# STlinkv21_STM8.net
KiCad netlist of a schematic drawn in Altium Designer
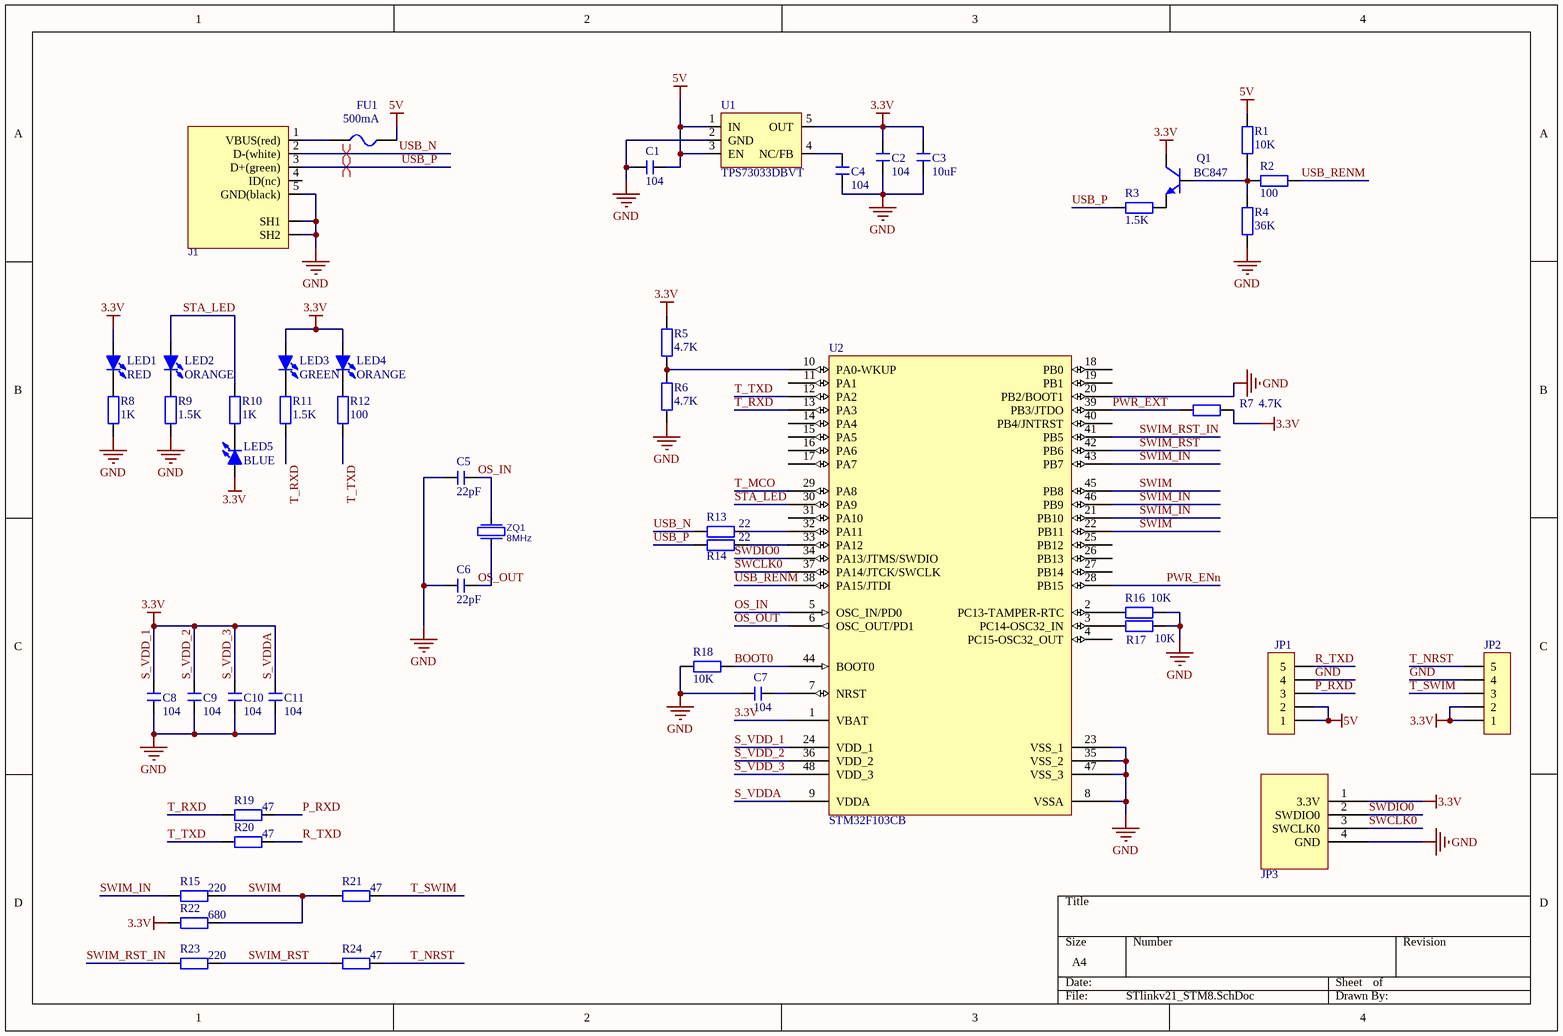
[diagram p0: STlinkv21_STM8.SchDoc]

(export (version "E")
  (design (tool "Eeschema 10.0.6"))
  (components
    (comp (ref "*") (value "JP3") (footprint "JP4") (libsource (lib "STlinkv21") (part "JP?")))
    (comp (ref "C1")
      (value "104")
      (footprint "C 0603_L")
      (description "无极性贴片电容")
      (fields (field (name "版权归属") "源创客"))
      (libsource (lib "3.1   - 电阻-电容-电感") (part "C"))
    )
    (comp (ref "C2")
      (value "104")
      (footprint "C 0603_L")
      (description "无极性贴片电容")
      (fields (field (name "版权归属") "源创客"))
      (libsource (lib "3.1   - 电阻-电容-电感") (part "C"))
    )
    (comp (ref "C3")
      (value "10uF")
      (footprint "C 0603_L")
      (description "无极性贴片电容")
      (fields (field (name "版权归属") "源创客"))
      (libsource (lib "3.1   - 电阻-电容-电感") (part "C"))
    )
    (comp (ref "C4")
      (value "104")
      (footprint "C 0603_L")
      (description "无极性贴片电容")
      (fields (field (name "版权归属") "源创客"))
      (libsource (lib "3.1   - 电阻-电容-电感") (part "C"))
    )
    (comp (ref "C5")
      (value "22pF")
      (footprint "C 0603_L")
      (description "无极性贴片电容")
      (fields (field (name "版权归属") "源创客"))
      (libsource (lib "3.1   - 电阻-电容-电感") (part "C"))
    )
    (comp (ref "C6")
      (value "22pF")
      (footprint "C 0603_L")
      (description "无极性贴片电容")
      (fields (field (name "版权归属") "源创客"))
      (libsource (lib "3.1   - 电阻-电容-电感") (part "C"))
    )
    (comp (ref "C7")
      (value "104")
      (footprint "C 0603_L")
      (description "无极性贴片电容")
      (fields (field (name "版权归属") "源创客"))
      (libsource (lib "3.1   - 电阻-电容-电感") (part "C"))
    )
    (comp (ref "C8")
      (value "104")
      (footprint "C 0603_L")
      (description "无极性贴片电容")
      (fields (field (name "版权归属") "源创客"))
      (libsource (lib "3.1   - 电阻-电容-电感") (part "C"))
    )
    (comp (ref "C9")
      (value "104")
      (footprint "C 0603_L")
      (description "无极性贴片电容")
      (fields (field (name "版权归属") "源创客"))
      (libsource (lib "3.1   - 电阻-电容-电感") (part "C"))
    )
    (comp (ref "C10")
      (value "104")
      (footprint "C 0603_L")
      (description "无极性贴片电容")
      (fields (field (name "版权归属") "源创客"))
      (libsource (lib "3.1   - 电阻-电容-电感") (part "C"))
    )
    (comp (ref "C11")
      (value "104")
      (footprint "C 0603_L")
      (description "无极性贴片电容")
      (fields (field (name "版权归属") "源创客"))
      (libsource (lib "3.1   - 电阻-电容-电感") (part "C"))
    )
    (comp (ref "FU1")
      (value "500mA")
      (footprint "FU 0805")
      (description "贴片保险丝")
      (fields (field (name "版权归属") "源创客"))
      (libsource (lib "10.1 - 保险丝-晶振") (part "FU"))
    )
    (comp (ref "J1")
      (value "microUSB 5BFR")
      (footprint "usbmicro B")
      (fields (field (name "LIBRARYNAME") "Nikitin (Exeland)"))
      (libsource (lib "Nikitin") (part "microUSB 5BFR"))
    )
    (comp (ref "JP1")
      (value "P_BOTTOM")
      (footprint "JP5Bottom")
      (description "5P接插件")
      (fields (field (name "版权归属") "源创客"))
      (libsource (lib "") (part "Header 5_1"))
    )
    (comp (ref "JP2")
      (value "P_BOTTOM")
      (footprint "JP5Bottom")
      (description "5P接插件")
      (fields (field (name "版权归属") "源创客"))
      (libsource (lib "4.5   - 接插件-脚距2.54") (part "Header 5"))
    )
    (comp (ref "LED1")
      (value "RED")
      (footprint "LED 0603B")
      (description "贴片LED")
      (fields (field (name "版权归属") "源创客"))
      (libsource (lib "9.1   - LED") (part "LED-SMD"))
    )
    (comp (ref "LED2")
      (value "ORANGE")
      (footprint "LED 0603B")
      (description "贴片LED")
      (fields (field (name "版权归属") "源创客"))
      (libsource (lib "9.1   - LED") (part "LED-SMD"))
    )
    (comp (ref "LED3")
      (value "GREEN")
      (footprint "LED 0603B")
      (description "贴片LED")
      (fields (field (name "版权归属") "源创客"))
      (libsource (lib "9.1   - LED") (part "LED-SMD"))
    )
    (comp (ref "LED4")
      (value "ORANGE")
      (footprint "LED 0603B")
      (description "贴片LED")
      (fields (field (name "版权归属") "源创客"))
      (libsource (lib "9.1   - LED") (part "LED-SMD"))
    )
    (comp (ref "LED5")
      (value "BLUE")
      (footprint "LED 0603B")
      (description "贴片LED")
      (fields (field (name "版权归属") "LED 0603 BLUE"))
      (libsource (lib "9.1   - LED") (part "LED-SMD"))
    )
    (comp (ref "Q1")
      (value "BC847")
      (footprint "SOT23-3N")
      (description "高频放大-NPN型")
      (fields (field (name "版权归属") "源创客"))
      (libsource (lib "6.2   - 三极管") (part "8050-SMD"))
    )
    (comp (ref "R1")
      (value "10K")
      (footprint "R 0603_L")
      (description "贴片电阻")
      (fields (field (name "版权归属") "源创客"))
      (libsource (lib "3.1   - 电阻-电容-电感") (part "R"))
    )
    (comp (ref "R2")
      (value "100")
      (footprint "R 0603_L")
      (description "贴片电阻")
      (fields (field (name "版权归属") "源创客"))
      (libsource (lib "3.1   - 电阻-电容-电感") (part "R"))
    )
    (comp (ref "R3")
      (value "1.5K")
      (footprint "R 0603_L")
      (description "贴片电阻")
      (fields (field (name "版权归属") "源创客"))
      (libsource (lib "3.1   - 电阻-电容-电感") (part "R"))
    )
    (comp (ref "R4")
      (value "36K")
      (footprint "R 0603_L")
      (description "贴片电阻")
      (fields (field (name "版权归属") "源创客"))
      (libsource (lib "3.1   - 电阻-电容-电感") (part "R"))
    )
    (comp (ref "R5")
      (value "4.7K")
      (footprint "R 0603_L")
      (description "贴片电阻")
      (fields (field (name "版权归属") "源创客"))
      (libsource (lib "3.1   - 电阻-电容-电感") (part "R"))
    )
    (comp (ref "R6")
      (value "4.7K")
      (footprint "R 0603_L")
      (description "贴片电阻")
      (fields (field (name "版权归属") "源创客"))
      (libsource (lib "3.1   - 电阻-电容-电感") (part "R"))
    )
    (comp (ref "R7")
      (value "4.7K")
      (footprint "R 0603_L")
      (description "贴片电阻")
      (fields (field (name "版权归属") "源创客"))
      (libsource (lib "3.1   - 电阻-电容-电感") (part "R"))
    )
    (comp (ref "R8")
      (value "1K")
      (footprint "R 0603_L")
      (description "贴片电阻")
      (fields (field (name "版权归属") "源创客"))
      (libsource (lib "3.1   - 电阻-电容-电感") (part "R"))
    )
    (comp (ref "R9")
      (value "1.5K")
      (footprint "R 0603_L")
      (description "贴片电阻")
      (fields (field (name "版权归属") "源创客"))
      (libsource (lib "3.1   - 电阻-电容-电感") (part "R"))
    )
    (comp (ref "R10")
      (value "1K")
      (footprint "R 0603_L")
      (description "贴片电阻")
      (fields (field (name "版权归属") "源创客"))
      (libsource (lib "3.1   - 电阻-电容-电感") (part "R"))
    )
    (comp (ref "R11")
      (value "1.5K")
      (footprint "R 0603_L")
      (description "贴片电阻")
      (fields (field (name "版权归属") "源创客"))
      (libsource (lib "3.1   - 电阻-电容-电感") (part "R"))
    )
    (comp (ref "R12")
      (value "100")
      (footprint "R 0603_L")
      (description "贴片电阻")
      (fields (field (name "版权归属") "源创客"))
      (libsource (lib "3.1   - 电阻-电容-电感") (part "R"))
    )
    (comp (ref "R13")
      (value "22")
      (footprint "R 0603_L")
      (description "贴片电阻")
      (fields (field (name "版权归属") "源创客"))
      (libsource (lib "3.1   - 电阻-电容-电感") (part "R"))
    )
    (comp (ref "R14")
      (value "22")
      (footprint "R 0603_L")
      (description "贴片电阻")
      (fields (field (name "版权归属") "源创客"))
      (libsource (lib "3.1   - 电阻-电容-电感") (part "R"))
    )
    (comp (ref "R15")
      (value "220")
      (footprint "R 0603_L")
      (description "贴片电阻")
      (fields (field (name "版权归属") "源创客"))
      (libsource (lib "3.1   - 电阻-电容-电感") (part "R"))
    )
    (comp (ref "R16")
      (value "10K")
      (footprint "R 0603_L")
      (description "贴片电阻")
      (fields (field (name "版权归属") "源创客"))
      (libsource (lib "3.1   - 电阻-电容-电感") (part "R"))
    )
    (comp (ref "R17")
      (value "10K")
      (footprint "R 0603_L")
      (description "贴片电阻")
      (fields (field (name "版权归属") "源创客"))
      (libsource (lib "3.1   - 电阻-电容-电感") (part "R"))
    )
    (comp (ref "R18")
      (value "10K")
      (footprint "R 0603_L")
      (description "贴片电阻")
      (fields (field (name "版权归属") "源创客"))
      (libsource (lib "3.1   - 电阻-电容-电感") (part "R"))
    )
    (comp (ref "R19")
      (value "47")
      (footprint "R 0603_L")
      (description "贴片电阻")
      (fields (field (name "版权归属") "源创客"))
      (libsource (lib "3.1   - 电阻-电容-电感") (part "R"))
    )
    (comp (ref "R20")
      (value "47")
      (footprint "R 0603_L")
      (description "贴片电阻")
      (fields (field (name "版权归属") "源创客"))
      (libsource (lib "3.1   - 电阻-电容-电感") (part "R"))
    )
    (comp (ref "R21")
      (value "47")
      (footprint "R 0603_L")
      (description "贴片电阻")
      (fields (field (name "版权归属") "源创客"))
      (libsource (lib "3.1   - 电阻-电容-电感") (part "R"))
    )
    (comp (ref "R22")
      (value "680")
      (footprint "R 0603_L")
      (description "贴片电阻")
      (fields (field (name "版权归属") "源创客"))
      (libsource (lib "3.1   - 电阻-电容-电感") (part "R"))
    )
    (comp (ref "R23")
      (value "220")
      (footprint "R 0603_L")
      (description "贴片电阻")
      (fields (field (name "版权归属") "源创客"))
      (libsource (lib "3.1   - 电阻-电容-电感") (part "R"))
    )
    (comp (ref "R24")
      (value "47")
      (footprint "R 0603_L")
      (description "贴片电阻")
      (fields (field (name "版权归属") "源创客"))
      (libsource (lib "3.1   - 电阻-电容-电感") (part "R"))
    )
    (comp (ref "U1")
      (value "TPS73033DBVT")
      (footprint "SOT-23-5")
      (fields (field (name "LIBRARYNAME") "Nikitin (Exeland)"))
      (libsource (lib "Nikitin") (part "TPS73033DBVT"))
    )
    (comp (ref "U2")
      (value "STM32F103CB")
      (footprint "LQFP48 7X7_L")
      (description "Flaah:64/RAM:20/IO:36")
      (fields (field (name "版权归属") "源创客"))
      (libsource (lib "2.1   - STM32系列单片机") (part "STM32F103C8"))
    )
    (comp (ref "ZQ1")
      (value "8MHz")
      (footprint "KX-13")
      (description "KX-13")
      (fields (field (name "LIBRARYNAME") "Nikitin (Exeland)"))
      (libsource (lib "Nikitin") (part "KX-13"))
    )
  )
  (nets
    (net (code "1") (name "/BOOT0") (class "Default")
      (node (ref "R18") (pin "1") (pinfunction "1_1") (pintype "passive"))
      (node (ref "U2") (pin "44") (pinfunction "BOOT0_44") (pintype "input"))
    )
    (net (code "2") (name "/OS_IN") (class "Default")
      (node (ref "C5") (pin "2") (pinfunction "2_2") (pintype "passive"))
      (node (ref "U2") (pin "5") (pinfunction "OSC_IN/PD0_5") (pintype "input"))
      (node (ref "ZQ1") (pin "4") (pintype "passive"))
    )
    (net (code "3") (name "/OS_OUT") (class "Default")
      (node (ref "C6") (pin "2") (pinfunction "2_2") (pintype "passive"))
      (node (ref "U2") (pin "6") (pinfunction "OSC_OUT/PD1_6") (pintype "output"))
      (node (ref "ZQ1") (pin "2") (pintype "passive"))
    )
    (net (code "4") (name "/PWR_ENn") (class "Default")
      (node (ref "U2") (pin "28") (pinfunction "PB15_28") (pintype "bidirectional"))
    )
    (net (code "5") (name "/PWR_EXT") (class "Default")
      (node (ref "R7") (pin "1") (pinfunction "1_1") (pintype "passive"))
      (node (ref "U2") (pin "39") (pinfunction "PB3/JTDO_39") (pintype "bidirectional"))
    )
    (net (code "6") (name "/P_RXD") (class "Default")
      (node (ref "JP1") (pin "3") (pinfunction "3_3") (pintype "passive"))
      (node (ref "R19") (pin "1") (pinfunction "1_1") (pintype "passive"))
    )
    (net (code "7") (name "/R_TXD") (class "Default")
      (node (ref "JP1") (pin "5") (pinfunction "5_5") (pintype "passive"))
      (node (ref "R20") (pin "1") (pinfunction "1_1") (pintype "passive"))
    )
    (net (code "8") (name "/STA_LED") (class "Default")
      (node (ref "LED2") (pin "1") (pinfunction "A_1") (pintype "passive"))
      (node (ref "R10") (pin "2") (pinfunction "2_2") (pintype "passive"))
      (node (ref "U2") (pin "30") (pinfunction "PA9_30") (pintype "bidirectional"))
    )
    (net (code "9") (name "/SWCLK0") (class "Default")
      (node (ref "*") (pin "3") (pinfunction "SWCLK0_3") (pintype "passive"))
      (node (ref "U2") (pin "37") (pinfunction "PA14/JTCK/SWCLK_37") (pintype "bidirectional"))
    )
    (net (code "10") (name "/SWDIO0") (class "Default")
      (node (ref "*") (pin "2") (pinfunction "SWDIO0_2") (pintype "passive"))
      (node (ref "U2") (pin "34") (pinfunction "PA13/JTMS/SWDIO_34") (pintype "bidirectional"))
    )
    (net (code "11") (name "/SWIM") (class "Default")
      (node (ref "R15") (pin "1") (pinfunction "1_1") (pintype "passive"))
      (node (ref "R21") (pin "2") (pinfunction "2_2") (pintype "passive"))
      (node (ref "R22") (pin "1") (pinfunction "1_1") (pintype "passive"))
      (node (ref "U2") (pin "22") (pinfunction "PB11_22") (pintype "bidirectional"))
      (node (ref "U2") (pin "45") (pinfunction "PB8_45") (pintype "bidirectional"))
    )
    (net (code "12") (name "/SWIM_IN") (class "Default")
      (node (ref "R15") (pin "2") (pinfunction "2_2") (pintype "passive"))
      (node (ref "U2") (pin "21") (pinfunction "PB10_21") (pintype "bidirectional"))
      (node (ref "U2") (pin "43") (pinfunction "PB7_43") (pintype "bidirectional"))
      (node (ref "U2") (pin "46") (pinfunction "PB9_46") (pintype "bidirectional"))
    )
    (net (code "13") (name "/SWIM_RST") (class "Default")
      (node (ref "R23") (pin "1") (pinfunction "1_1") (pintype "passive"))
      (node (ref "R24") (pin "2") (pinfunction "2_2") (pintype "passive"))
      (node (ref "U2") (pin "42") (pinfunction "PB6_42") (pintype "bidirectional"))
    )
    (net (code "14") (name "/SWIM_RST_IN") (class "Default")
      (node (ref "R23") (pin "2") (pinfunction "2_2") (pintype "passive"))
      (node (ref "U2") (pin "41") (pinfunction "PB5_41") (pintype "bidirectional"))
    )
    (net (code "15") (name "/T_MCO") (class "Default")
      (node (ref "U2") (pin "29") (pinfunction "PA8_29") (pintype "bidirectional"))
    )
    (net (code "16") (name "/T_NRST") (class "Default")
      (node (ref "JP2") (pin "5") (pinfunction "5_5") (pintype "passive"))
      (node (ref "R24") (pin "1") (pinfunction "1_1") (pintype "passive"))
    )
    (net (code "17") (name "/T_RXD") (class "Default")
      (node (ref "R11") (pin "1") (pinfunction "1_1") (pintype "passive"))
      (node (ref "R19") (pin "2") (pinfunction "2_2") (pintype "passive"))
      (node (ref "U2") (pin "13") (pinfunction "PA3_13") (pintype "bidirectional"))
    )
    (net (code "18") (name "/T_SWIM") (class "Default")
      (node (ref "JP2") (pin "3") (pinfunction "3_3") (pintype "passive"))
      (node (ref "R21") (pin "1") (pinfunction "1_1") (pintype "passive"))
    )
    (net (code "19") (name "/T_TXD") (class "Default")
      (node (ref "R12") (pin "1") (pinfunction "1_1") (pintype "passive"))
      (node (ref "R20") (pin "2") (pinfunction "2_2") (pintype "passive"))
      (node (ref "U2") (pin "12") (pinfunction "PA2_12") (pintype "bidirectional"))
    )
    (net (code "20") (name "/USB_N") (class "Default")
      (node (ref "J1") (pin "2") (pinfunction "D-(white)_2") (pintype "passive"))
      (node (ref "R13") (pin "2") (pinfunction "2_2") (pintype "passive"))
    )
    (net (code "21") (name "/USB_P") (class "Default")
      (node (ref "J1") (pin "3") (pinfunction "D+(green)_3") (pintype "passive"))
      (node (ref "R14") (pin "2") (pinfunction "2_2") (pintype "passive"))
      (node (ref "R3") (pin "1") (pinfunction "1_1") (pintype "passive"))
    )
    (net (code "22") (name "/USB_RENM") (class "Default")
      (node (ref "R2") (pin "2") (pinfunction "2_2") (pintype "passive"))
      (node (ref "U2") (pin "38") (pinfunction "PA15/JTDI_38") (pintype "bidirectional"))
    )
    (net (code "23") (name "3.3V") (class "Default")
      (node (ref "*") (pin "1") (pinfunction "3.3V_1") (pintype "passive"))
      (node (ref "C10") (pin "2") (pinfunction "2_2") (pintype "passive"))
      (node (ref "C11") (pin "2") (pinfunction "2_2") (pintype "passive"))
      (node (ref "C2") (pin "2") (pinfunction "2_2") (pintype "passive"))
      (node (ref "C3") (pin "2") (pinfunction "2_2") (pintype "passive"))
      (node (ref "C8") (pin "2") (pinfunction "2_2") (pintype "passive"))
      (node (ref "C9") (pin "2") (pinfunction "2_2") (pintype "passive"))
      (node (ref "JP2") (pin "1") (pinfunction "1_1") (pintype "passive"))
      (node (ref "JP2") (pin "2") (pinfunction "2_2") (pintype "passive"))
      (node (ref "LED1") (pin "1") (pinfunction "A_1") (pintype "passive"))
      (node (ref "LED3") (pin "1") (pinfunction "A_1") (pintype "passive"))
      (node (ref "LED4") (pin "1") (pinfunction "A_1") (pintype "passive"))
      (node (ref "LED5") (pin "1") (pinfunction "A_1") (pintype "passive"))
      (node (ref "Q1") (pin "3") (pinfunction "C_3") (pintype "passive"))
      (node (ref "R22") (pin "2") (pinfunction "2_2") (pintype "passive"))
      (node (ref "R5") (pin "2") (pinfunction "2_2") (pintype "passive"))
      (node (ref "R7") (pin "2") (pinfunction "2_2") (pintype "passive"))
      (node (ref "U1") (pin "5") (pinfunction "OUT_5") (pintype "passive"))
      (node (ref "U2") (pin "1") (pinfunction "VBAT_1") (pintype "power_in"))
      (node (ref "U2") (pin "24") (pinfunction "VDD_1_24") (pintype "power_in"))
      (node (ref "U2") (pin "36") (pinfunction "VDD_2_36") (pintype "power_in"))
      (node (ref "U2") (pin "48") (pinfunction "VDD_3_48") (pintype "power_in"))
      (node (ref "U2") (pin "9") (pinfunction "VDDA_9") (pintype "power_in"))
    )
    (net (code "24") (name "5V") (class "Default")
      (node (ref "C1") (pin "2") (pinfunction "2_2") (pintype "passive"))
      (node (ref "FU1") (pin "2") (pinfunction "2_2") (pintype "passive"))
      (node (ref "JP1") (pin "1") (pinfunction "1_1") (pintype "passive"))
      (node (ref "JP1") (pin "2") (pinfunction "2_2") (pintype "passive"))
      (node (ref "R1") (pin "2") (pinfunction "2_2") (pintype "passive"))
      (node (ref "U1") (pin "1") (pinfunction "IN_1") (pintype "passive"))
      (node (ref "U1") (pin "3") (pinfunction "EN_3") (pintype "passive"))
    )
    (net (code "25") (name "GND") (class "Default")
      (node (ref "*") (pin "4") (pinfunction "GND_4") (pintype "passive"))
      (node (ref "C1") (pin "1") (pinfunction "1_1") (pintype "passive"))
      (node (ref "C10") (pin "1") (pinfunction "1_1") (pintype "passive"))
      (node (ref "C11") (pin "1") (pinfunction "1_1") (pintype "passive"))
      (node (ref "C2") (pin "1") (pinfunction "1_1") (pintype "passive"))
      (node (ref "C3") (pin "1") (pinfunction "1_1") (pintype "passive"))
      (node (ref "C4") (pin "1") (pinfunction "1_1") (pintype "passive"))
      (node (ref "C5") (pin "1") (pinfunction "1_1") (pintype "passive"))
      (node (ref "C6") (pin "1") (pinfunction "1_1") (pintype "passive"))
      (node (ref "C7") (pin "1") (pinfunction "1_1") (pintype "passive"))
      (node (ref "C8") (pin "1") (pinfunction "1_1") (pintype "passive"))
      (node (ref "C9") (pin "1") (pinfunction "1_1") (pintype "passive"))
      (node (ref "J1") (pin "11") (pinfunction "SH2_11") (pintype "passive"))
      (node (ref "J1") (pin "5") (pinfunction "GND(black)_5") (pintype "passive"))
      (node (ref "J1") (pin "8") (pinfunction "SH1_8") (pintype "passive"))
      (node (ref "JP1") (pin "4") (pinfunction "4_4") (pintype "passive"))
      (node (ref "JP2") (pin "4") (pinfunction "4_4") (pintype "passive"))
      (node (ref "R16") (pin "1") (pinfunction "1_1") (pintype "passive"))
      (node (ref "R17") (pin "1") (pinfunction "1_1") (pintype "passive"))
      (node (ref "R18") (pin "2") (pinfunction "2_2") (pintype "passive"))
      (node (ref "R4") (pin "1") (pinfunction "1_1") (pintype "passive"))
      (node (ref "R6") (pin "1") (pinfunction "1_1") (pintype "passive"))
      (node (ref "R8") (pin "1") (pinfunction "1_1") (pintype "passive"))
      (node (ref "R9") (pin "1") (pinfunction "1_1") (pintype "passive"))
      (node (ref "U1") (pin "2") (pinfunction "GND_2") (pintype "passive"))
      (node (ref "U2") (pin "20") (pinfunction "PB2/BOOT1_20") (pintype "bidirectional"))
      (node (ref "U2") (pin "23") (pinfunction "VSS_1_23") (pintype "power_in"))
      (node (ref "U2") (pin "35") (pinfunction "VSS_2_35") (pintype "power_in"))
      (node (ref "U2") (pin "47") (pinfunction "VSS_3_47") (pintype "power_in"))
      (node (ref "U2") (pin "8") (pinfunction "VSSA_8") (pintype "power_in"))
    )
    (net (code "26") (name "Net-(J1-VBUS(red))") (class "Default")
      (node (ref "FU1") (pin "1") (pinfunction "1_1") (pintype "passive"))
      (node (ref "J1") (pin "1") (pinfunction "VBUS(red)_1") (pintype "passive"))
    )
    (net (code "27") (name "Net-(LED1-K)") (class "Default")
      (node (ref "LED1") (pin "2") (pinfunction "K_2") (pintype "passive"))
      (node (ref "R8") (pin "2") (pinfunction "2_2") (pintype "passive"))
    )
    (net (code "28") (name "Net-(LED2-K)") (class "Default")
      (node (ref "LED2") (pin "2") (pinfunction "K_2") (pintype "passive"))
      (node (ref "R9") (pin "2") (pinfunction "2_2") (pintype "passive"))
    )
    (net (code "29") (name "Net-(LED3-K)") (class "Default")
      (node (ref "LED3") (pin "2") (pinfunction "K_2") (pintype "passive"))
      (node (ref "R11") (pin "2") (pinfunction "2_2") (pintype "passive"))
    )
    (net (code "30") (name "Net-(LED4-K)") (class "Default")
      (node (ref "LED4") (pin "2") (pinfunction "K_2") (pintype "passive"))
      (node (ref "R12") (pin "2") (pinfunction "2_2") (pintype "passive"))
    )
    (net (code "31") (name "Net-(LED5-K)") (class "Default")
      (node (ref "LED5") (pin "2") (pinfunction "K_2") (pintype "passive"))
      (node (ref "R10") (pin "1") (pinfunction "1_1") (pintype "passive"))
    )
    (net (code "32") (name "Net-(Q1-B)") (class "Default")
      (node (ref "Q1") (pin "1") (pinfunction "B_1") (pintype "passive"))
      (node (ref "R1") (pin "1") (pinfunction "1_1") (pintype "passive"))
      (node (ref "R2") (pin "1") (pinfunction "1_1") (pintype "passive"))
      (node (ref "R4") (pin "2") (pinfunction "2_2") (pintype "passive"))
    )
    (net (code "33") (name "Net-(Q1-E)") (class "Default")
      (node (ref "Q1") (pin "2") (pinfunction "E_2") (pintype "passive"))
      (node (ref "R3") (pin "2") (pinfunction "2_2") (pintype "passive"))
    )
    (net (code "34") (name "Net-(U1-NC{slash}FB)") (class "Default")
      (node (ref "C4") (pin "2") (pinfunction "2_2") (pintype "passive"))
      (node (ref "U1") (pin "4") (pinfunction "NC/FB_4") (pintype "passive"))
    )
    (net (code "35") (name "Net-(U2-NRST)") (class "Default")
      (node (ref "C7") (pin "2") (pinfunction "2_2") (pintype "passive"))
      (node (ref "U2") (pin "7") (pinfunction "NRST_7") (pintype "bidirectional"))
    )
    (net (code "36") (name "Net-(U2-PA0-WKUP)") (class "Default")
      (node (ref "R5") (pin "1") (pinfunction "1_1") (pintype "passive"))
      (node (ref "R6") (pin "2") (pinfunction "2_2") (pintype "passive"))
      (node (ref "U2") (pin "10") (pinfunction "PA0-WKUP_10") (pintype "bidirectional"))
    )
    (net (code "37") (name "Net-(U2-PA11)") (class "Default")
      (node (ref "R13") (pin "1") (pinfunction "1_1") (pintype "passive"))
      (node (ref "U2") (pin "32") (pinfunction "PA11_32") (pintype "bidirectional"))
    )
    (net (code "38") (name "Net-(U2-PA12)") (class "Default")
      (node (ref "R14") (pin "1") (pinfunction "1_1") (pintype "passive"))
      (node (ref "U2") (pin "33") (pinfunction "PA12_33") (pintype "bidirectional"))
    )
    (net (code "39") (name "Net-(U2-PC13-TAMPER-RTC)") (class "Default")
      (node (ref "R16") (pin "2") (pinfunction "2_2") (pintype "passive"))
      (node (ref "U2") (pin "2") (pinfunction "PC13-TAMPER-RTC_2") (pintype "bidirectional"))
    )
    (net (code "40") (name "Net-(U2-PC14-OSC32_IN)") (class "Default")
      (node (ref "R17") (pin "2") (pinfunction "2_2") (pintype "passive"))
      (node (ref "U2") (pin "3") (pinfunction "PC14-OSC32_IN_3") (pintype "bidirectional"))
    )
    (net (code "41") (name "unconnected-(J1-ID(nc)-Pad4)") (class "Default")
      (node (ref "J1") (pin "4") (pinfunction "ID(nc)_4") (pintype "passive"))
    )
    (net (code "42") (name "unconnected-(U2-PA1-Pad11)") (class "Default")
      (node (ref "U2") (pin "11") (pinfunction "PA1_11") (pintype "bidirectional"))
    )
    (net (code "43") (name "unconnected-(U2-PA4-Pad14)") (class "Default")
      (node (ref "U2") (pin "14") (pinfunction "PA4_14") (pintype "bidirectional"))
    )
    (net (code "44") (name "unconnected-(U2-PA5-Pad15)") (class "Default")
      (node (ref "U2") (pin "15") (pinfunction "PA5_15") (pintype "bidirectional"))
    )
    (net (code "45") (name "unconnected-(U2-PA6-Pad16)") (class "Default")
      (node (ref "U2") (pin "16") (pinfunction "PA6_16") (pintype "bidirectional"))
    )
    (net (code "46") (name "unconnected-(U2-PA7-Pad17)") (class "Default")
      (node (ref "U2") (pin "17") (pinfunction "PA7_17") (pintype "bidirectional"))
    )
    (net (code "47") (name "unconnected-(U2-PA10-Pad31)") (class "Default")
      (node (ref "U2") (pin "31") (pinfunction "PA10_31") (pintype "bidirectional"))
    )
    (net (code "48") (name "unconnected-(U2-PB0-Pad18)") (class "Default")
      (node (ref "U2") (pin "18") (pinfunction "PB0_18") (pintype "bidirectional"))
    )
    (net (code "49") (name "unconnected-(U2-PB1-Pad19)") (class "Default")
      (node (ref "U2") (pin "19") (pinfunction "PB1_19") (pintype "bidirectional"))
    )
    (net (code "50") (name "unconnected-(U2-PB4{slash}JNTRST-Pad40)") (class "Default")
      (node (ref "U2") (pin "40") (pinfunction "PB4/JNTRST_40") (pintype "bidirectional"))
    )
    (net (code "51") (name "unconnected-(U2-PB12-Pad25)") (class "Default")
      (node (ref "U2") (pin "25") (pinfunction "PB12_25") (pintype "bidirectional"))
    )
    (net (code "52") (name "unconnected-(U2-PB13-Pad26)") (class "Default")
      (node (ref "U2") (pin "26") (pinfunction "PB13_26") (pintype "bidirectional"))
    )
    (net (code "53") (name "unconnected-(U2-PB14-Pad27)") (class "Default")
      (node (ref "U2") (pin "27") (pinfunction "PB14_27") (pintype "bidirectional"))
    )
    (net (code "54") (name "unconnected-(U2-PC15-OSC32_OUT-Pad4)") (class "Default")
      (node (ref "U2") (pin "4") (pinfunction "PC15-OSC32_OUT_4") (pintype "bidirectional"))
    )
    (net (code "55") (name "unconnected-(ZQ1-Pad1)") (class "Default")
      (node (ref "ZQ1") (pin "1") (pintype "passive"))
    )
    (net (code "56") (name "unconnected-(ZQ1-Pad3)") (class "Default")
      (node (ref "ZQ1") (pin "3") (pintype "passive"))
    )
  )
)
